# cSLIM_RS485.net
KiCad netlist of a schematic drawn in Altium Designer
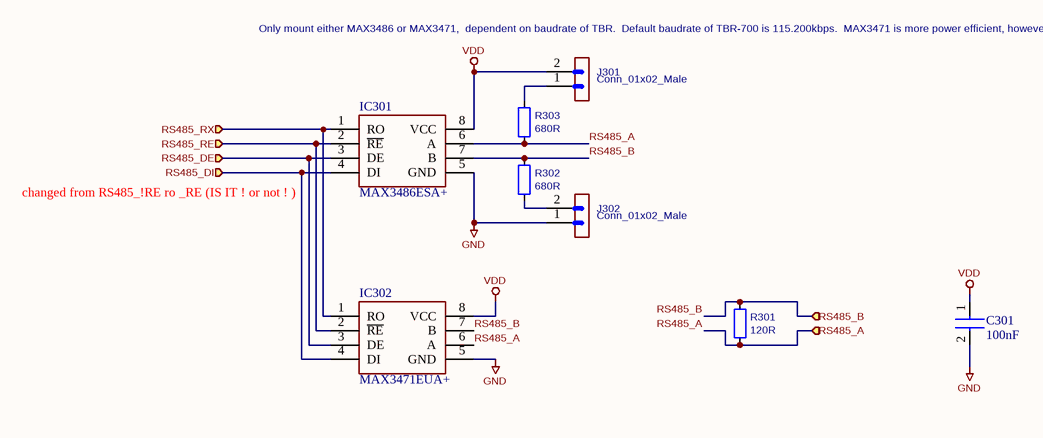
[diagram p0: cSLIM_RS485.SchDoc]

(export (version "E")
  (design (tool "Eeschema 10.0.6"))
  (components
    (comp (ref "C301")
      (value "100nF")
      (footprint "cSLIM-SA:CAPC1608X90N")
      (description "Capacitor")
      (fields
        (field (name "MANUFACTURER_PART_NUMBER") "06033G104ZAT2A")
        (field (name "MOUSER PART NUMBER") "581-06033G104Z")
      )
      (libsource (lib "cSLIM-SA") (part "C"))
    )
    (comp (ref "IC301")
      (value "MAX3486ESA+")
      (footprint "cSLIM-SA:SOIC127P600X175-8N")
      (description "Integrated Circuit")
      (fields (field (name "MOUSER PART NUMBER") "700-MAX3486ESA"))
      (libsource (lib "cSLIM-SA") (part "MAX3486ESA+"))
    )
    (comp (ref "IC302")
      (value "MAX3471EUA+")
      (footprint "cSLIM-SA:SOP65P490X110-8N")
      (description "Integrated Circuit")
      (fields (field (name "MOUSER PART NUMBER") "700-MAX3471EUA"))
      (libsource (lib "cSLIM-SA") (part "MAX3471EUA+"))
    )
    (comp (ref "J301")
      (value "Conn_01x02_Male")
      (footprint "cSLIM-SA:HDRV2W110P0X254_1X2_508X254X854P")
      (description "Connector")
      (fields
        (field (name "MANUFACTURER_PART_NUMBER") "61300211121")
        (field (name "MOUSER PART NUMBER") "710-61300211121")
      )
      (libsource (lib "cSLIM-SA") (part "61300211121"))
    )
    (comp (ref "J302")
      (value "Conn_01x02_Male")
      (footprint "cSLIM-SA:HDRV2W110P0X254_1X2_508X254X854P")
      (description "Connector")
      (fields
        (field (name "MANUFACTURER_PART_NUMBER") "61300211121")
        (field (name "MOUSER PART NUMBER") "710-61300211121")
      )
      (libsource (lib "cSLIM-SA") (part "61300211121"))
    )
    (comp (ref "R301") (value "120R") (footprint "RESC1608X55N") (libsource (lib "cSLIM-SA") (part "R")))
    (comp (ref "R302") (value "680R") (footprint "RESC1608X55N") (libsource (lib "cSLIM-SA") (part "R")))
    (comp (ref "R303") (value "680R") (footprint "RESC1608X55N") (libsource (lib "cSLIM-SA") (part "R")))
  )
  (nets
    (net (code "1") (name "/RS485_A") (class "Default")
      (node (ref "IC301") (pin "6") (pinfunction "A_6") (pintype "passive"))
      (node (ref "IC302") (pin "6") (pinfunction "A_6") (pintype "passive"))
      (node (ref "R301") (pin "2") (pinfunction "2_2") (pintype "passive"))
      (node (ref "R303") (pin "2") (pinfunction "2_2") (pintype "passive"))
    )
    (net (code "2") (name "/RS485_B") (class "Default")
      (node (ref "IC301") (pin "7") (pinfunction "B_7") (pintype "passive"))
      (node (ref "IC302") (pin "7") (pinfunction "B_7") (pintype "passive"))
      (node (ref "R301") (pin "1") (pinfunction "1_1") (pintype "passive"))
      (node (ref "R302") (pin "1") (pinfunction "1_1") (pintype "passive"))
    )
    (net (code "3") (name "/RS485_DE") (class "Default")
      (node (ref "IC301") (pin "3") (pinfunction "DE_3") (pintype "passive"))
      (node (ref "IC302") (pin "3") (pinfunction "DE_3") (pintype "passive"))
    )
    (net (code "4") (name "/RS485_DI") (class "Default")
      (node (ref "IC301") (pin "4") (pinfunction "DI_4") (pintype "passive"))
      (node (ref "IC302") (pin "4") (pinfunction "DI_4") (pintype "passive"))
    )
    (net (code "5") (name "/RS485_RE") (class "Default")
      (node (ref "IC301") (pin "2") (pinfunction "~{RE}_2") (pintype "passive"))
      (node (ref "IC302") (pin "2") (pinfunction "~{RE}_2") (pintype "passive"))
    )
    (net (code "6") (name "/RS485_RX") (class "Default")
      (node (ref "IC301") (pin "1") (pinfunction "RO_1") (pintype "passive"))
      (node (ref "IC302") (pin "1") (pinfunction "RO_1") (pintype "passive"))
    )
    (net (code "7") (name "GND") (class "Default")
      (node (ref "C301") (pin "2") (pinfunction "2_2") (pintype "passive"))
      (node (ref "IC301") (pin "5") (pinfunction "GND_5") (pintype "passive"))
      (node (ref "IC302") (pin "5") (pinfunction "GND_5") (pintype "passive"))
      (node (ref "J302") (pin "1") (pinfunction "1_1") (pintype "passive"))
    )
    (net (code "8") (name "Net-(J301-Pad1)") (class "Default")
      (node (ref "J301") (pin "1") (pinfunction "1_1") (pintype "passive"))
      (node (ref "R303") (pin "1") (pinfunction "1_1") (pintype "passive"))
    )
    (net (code "9") (name "Net-(J302-Pad2)") (class "Default")
      (node (ref "J302") (pin "2") (pinfunction "2_2") (pintype "passive"))
      (node (ref "R302") (pin "2") (pinfunction "2_2") (pintype "passive"))
    )
    (net (code "10") (name "VDD") (class "Default")
      (node (ref "C301") (pin "1") (pinfunction "1_1") (pintype "passive"))
      (node (ref "IC301") (pin "8") (pinfunction "VCC_8") (pintype "passive"))
      (node (ref "IC302") (pin "8") (pinfunction "VCC_8") (pintype "passive"))
      (node (ref "J301") (pin "2") (pinfunction "2_2") (pintype "passive"))
    )
  )
)
